# Wire_Finder.net
KiCad netlist of a schematic drawn in EAGLE
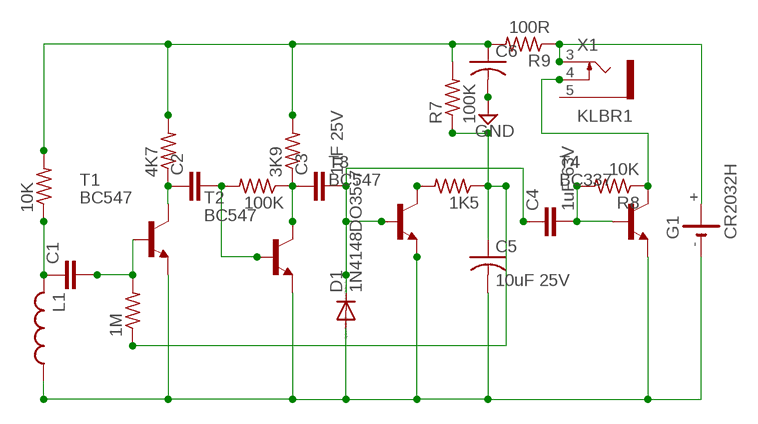
[diagram p0: schematic, sheet 1]

(export (version "E")
  (design (tool "Eeschema 10.0.6"))
  (components
    (comp (ref "1K5")
      (value "R-US_0204/7")
      (footprint "eagle-import:0204_7")
      (libsource (lib "eagle-import") (part "R-US_0204/7"))
    )
    (comp (ref "1M")
      (value "R-US_0204/7")
      (footprint "eagle-import:0204_7")
      (libsource (lib "eagle-import") (part "R-US_0204/7"))
    )
    (comp (ref "3K9")
      (value "R-US_0204/7")
      (footprint "eagle-import:0204_7")
      (libsource (lib "eagle-import") (part "R-US_0204/7"))
    )
    (comp (ref "4K7")
      (value "R-US_0204/7")
      (footprint "eagle-import:0204_7")
      (libsource (lib "eagle-import") (part "R-US_0204/7"))
    )
    (comp (ref "10K")
      (value "R-US_0204/7")
      (footprint "eagle-import:0204_7")
      (libsource (lib "eagle-import") (part "R-US_0204/7"))
    )
    (comp (ref "100K")
      (value "R-US_0204/7")
      (footprint "eagle-import:0204_7")
      (libsource (lib "eagle-import") (part "R-US_0204/7"))
    )
    (comp (ref "C1")
      (value "C2.5/2")
      (footprint "eagle-import:C2.5-2")
      (libsource (lib "eagle-import") (part "C2.5/2"))
    )
    (comp (ref "C2")
      (value "C2.5/2")
      (footprint "eagle-import:C2.5-2")
      (libsource (lib "eagle-import") (part "C2.5/2"))
    )
    (comp (ref "C3")
      (value "1uF 25V")
      (footprint "eagle-import:C2.5-2")
      (libsource (lib "eagle-import") (part "C2.5/2"))
    )
    (comp (ref "C4")
      (value "1uF 63V")
      (footprint "eagle-import:C2.5-2")
      (libsource (lib "eagle-import") (part "C2.5/2"))
    )
    (comp (ref "C5")
      (value "10uF 25V")
      (footprint "eagle-import:C025-024X044")
      (libsource (lib "eagle-import") (part "C-US025-024X044"))
    )
    (comp (ref "C6")
      (value "C-US025-024X044")
      (footprint "eagle-import:C025-024X044")
      (libsource (lib "eagle-import") (part "C-US025-024X044"))
    )
    (comp (ref "D1")
      (value "1N4148DO35-7")
      (footprint "eagle-import:DO35-7")
      (libsource (lib "eagle-import") (part "1N4148DO35-7"))
    )
    (comp (ref "G1")
      (value "CR2032H")
      (footprint "eagle-import:CR2032H")
      (libsource (lib "eagle-import") (part "CR2032H"))
    )
    (comp (ref "L1")
      (value "L-USIR-2")
      (footprint "eagle-import:IR-2")
      (libsource (lib "eagle-import") (part "L-USIR-2"))
    )
    (comp (ref "R7")
      (value "100K")
      (footprint "eagle-import:0204_7")
      (libsource (lib "eagle-import") (part "R-US_0204/7"))
    )
    (comp (ref "R8")
      (value "10K")
      (footprint "eagle-import:0204_7")
      (libsource (lib "eagle-import") (part "R-US_0204/7"))
    )
    (comp (ref "R9")
      (value "100R")
      (footprint "eagle-import:0204_7")
      (libsource (lib "eagle-import") (part "R-US_0204/7"))
    )
    (comp (ref "T1")
      (value "BC547")
      (footprint "eagle-import:TO92")
      (libsource (lib "eagle-import") (part "BC547"))
    )
    (comp (ref "T2")
      (value "BC547")
      (footprint "eagle-import:TO92")
      (libsource (lib "eagle-import") (part "BC547"))
    )
    (comp (ref "T3")
      (value "BC547")
      (footprint "eagle-import:TO92")
      (libsource (lib "eagle-import") (part "BC547"))
    )
    (comp (ref "T4")
      (value "BC337")
      (footprint "eagle-import:TO92")
      (libsource (lib "eagle-import") (part "BC337"))
    )
    (comp (ref "X1")
      (value "KLBR1")
      (footprint "eagle-import:KLBR1")
      (fields (field (name "MPN") "KLBR 1"))
      (libsource (lib "eagle-import") (part "KLBR?1"))
    )
  )
  (nets
    (net (code "1") (name "GND") (class "Default")
      (node (ref "C6") (pin "2") (pinfunction "2_2") (pintype "passive"))
    )
    (net (code "2") (name "Net-(1K5-Pad1)") (class "Default")
      (node (ref "1K5") (pin "1") (pinfunction "1_1") (pintype "passive"))
      (node (ref "1M") (pin "1") (pinfunction "1_1") (pintype "passive"))
      (node (ref "C5") (pin "1") (pinfunction "1_1") (pintype "passive"))
      (node (ref "R7") (pin "1") (pinfunction "1_1") (pintype "passive"))
    )
    (net (code "3") (name "Net-(10K-Pad1)") (class "Default")
      (node (ref "10K") (pin "1") (pinfunction "1_1") (pintype "passive"))
      (node (ref "C1") (pin "1") (pinfunction "1_1") (pintype "passive"))
      (node (ref "L1") (pin "2") (pinfunction "2_2") (pintype "passive"))
    )
    (net (code "4") (name "Net-(10K-Pad2)") (class "Default")
      (node (ref "10K") (pin "2") (pinfunction "2_2") (pintype "passive"))
      (node (ref "3K9") (pin "2") (pinfunction "2_2") (pintype "passive"))
      (node (ref "4K7") (pin "2") (pinfunction "2_2") (pintype "passive"))
      (node (ref "C6") (pin "1") (pinfunction "1_1") (pintype "passive"))
      (node (ref "R7") (pin "2") (pinfunction "2_2") (pintype "passive"))
      (node (ref "R9") (pin "2") (pinfunction "2_2") (pintype "passive"))
    )
    (net (code "5") (name "Net-(G1-+-Pad+@1)") (class "Default")
      (node (ref "G1") (pin "+") (pinfunction "+_+") (pintype "passive"))
      (node (ref "G1") (pin "+@1") (pinfunction "+_+@1") (pintype "passive"))
      (node (ref "R9") (pin "1") (pinfunction "1_1") (pintype "passive"))
      (node (ref "X1") (pin "3") (pinfunction "3_3") (pintype "passive"))
    )
    (net (code "6") (name "Net-(T1-B)") (class "Default")
      (node (ref "1M") (pin "2") (pinfunction "2_2") (pintype "passive"))
      (node (ref "C1") (pin "2") (pinfunction "2_2") (pintype "passive"))
      (node (ref "T1") (pin "2") (pinfunction "B_2") (pintype "passive"))
    )
    (net (code "7") (name "Net-(T1-C)") (class "Default")
      (node (ref "4K7") (pin "1") (pinfunction "1_1") (pintype "passive"))
      (node (ref "C2") (pin "1") (pinfunction "1_1") (pintype "passive"))
      (node (ref "T1") (pin "3") (pinfunction "C_3") (pintype "passive"))
    )
    (net (code "8") (name "Net-(T1-E)") (class "Default")
      (node (ref "C5") (pin "2") (pinfunction "2_2") (pintype "passive"))
      (node (ref "D1") (pin "A") (pinfunction "A_A") (pintype "passive"))
      (node (ref "G1") (pin "-") (pinfunction "-_-") (pintype "passive"))
      (node (ref "L1") (pin "1") (pinfunction "1_1") (pintype "passive"))
      (node (ref "T1") (pin "1") (pinfunction "E_1") (pintype "passive"))
      (node (ref "T2") (pin "1") (pinfunction "E_1") (pintype "passive"))
      (node (ref "T3") (pin "1") (pinfunction "E_1") (pintype "passive"))
      (node (ref "T4") (pin "1") (pinfunction "E_1") (pintype "passive"))
    )
    (net (code "9") (name "Net-(T2-B)") (class "Default")
      (node (ref "100K") (pin "2") (pinfunction "2_2") (pintype "passive"))
      (node (ref "C2") (pin "2") (pinfunction "2_2") (pintype "passive"))
      (node (ref "T2") (pin "2") (pinfunction "B_2") (pintype "passive"))
    )
    (net (code "10") (name "Net-(T2-C)") (class "Default")
      (node (ref "100K") (pin "1") (pinfunction "1_1") (pintype "passive"))
      (node (ref "3K9") (pin "1") (pinfunction "1_1") (pintype "passive"))
      (node (ref "C3") (pin "1") (pinfunction "1_1") (pintype "passive"))
      (node (ref "T2") (pin "3") (pinfunction "C_3") (pintype "passive"))
    )
    (net (code "11") (name "Net-(T3-B)") (class "Default")
      (node (ref "C3") (pin "2") (pinfunction "2_2") (pintype "passive"))
      (node (ref "C4") (pin "1") (pinfunction "1_1") (pintype "passive"))
      (node (ref "D1") (pin "C") (pinfunction "C_C") (pintype "passive"))
      (node (ref "T3") (pin "2") (pinfunction "B_2") (pintype "passive"))
    )
    (net (code "12") (name "Net-(T3-C)") (class "Default")
      (node (ref "1K5") (pin "2") (pinfunction "2_2") (pintype "passive"))
      (node (ref "T3") (pin "3") (pinfunction "C_3") (pintype "passive"))
    )
    (net (code "13") (name "Net-(T4-B)") (class "Default")
      (node (ref "C4") (pin "2") (pinfunction "2_2") (pintype "passive"))
      (node (ref "R8") (pin "2") (pinfunction "2_2") (pintype "passive"))
      (node (ref "T4") (pin "2") (pinfunction "B_2") (pintype "passive"))
    )
    (net (code "14") (name "Net-(T4-C)") (class "Default")
      (node (ref "R8") (pin "1") (pinfunction "1_1") (pintype "passive"))
      (node (ref "T4") (pin "3") (pinfunction "C_3") (pintype "passive"))
      (node (ref "X1") (pin "4") (pinfunction "4_4") (pintype "passive"))
    )
    (net (code "15") (name "unconnected-(X1-Pad5)") (class "Default")
      (node (ref "X1") (pin "5") (pinfunction "5_5") (pintype "passive"))
    )
  )
)
